# Body_Scale_v01.net
KiCad netlist of a schematic drawn in EAGLE
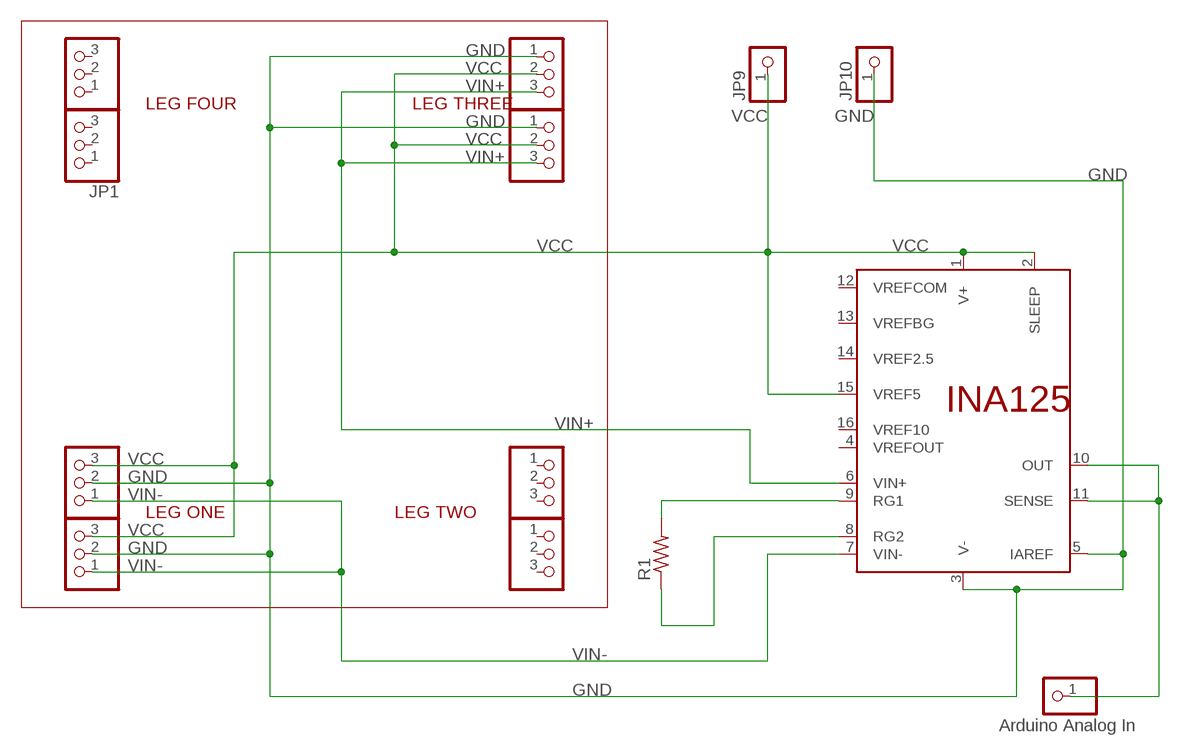
[diagram p0: schematic, sheet 1]

(export (version "E")
  (design (tool "Eeschema 10.0.6"))
  (components
    (comp (ref "IC1")
      (value "INA125")
      (footprint "eagle-import:DIL16")
      (libsource (lib "eagle-import") (part "INA125"))
    )
    (comp (ref "JP1")
      (value "PINHD-1X3")
      (footprint "eagle-import:1X03")
      (libsource (lib "eagle-import") (part "PINHD-1X3"))
    )
    (comp (ref "JP2")
      (value "PINHD-1X3")
      (footprint "eagle-import:1X03")
      (libsource (lib "eagle-import") (part "PINHD-1X3"))
    )
    (comp (ref "JP3")
      (value "PINHD-1X3")
      (footprint "eagle-import:1X03")
      (libsource (lib "eagle-import") (part "PINHD-1X3"))
    )
    (comp (ref "JP4")
      (value "PINHD-1X3")
      (footprint "eagle-import:1X03")
      (libsource (lib "eagle-import") (part "PINHD-1X3"))
    )
    (comp (ref "JP5")
      (value "PINHD-1X3")
      (footprint "eagle-import:1X03")
      (libsource (lib "eagle-import") (part "PINHD-1X3"))
    )
    (comp (ref "JP6")
      (value "PINHD-1X3")
      (footprint "eagle-import:1X03")
      (libsource (lib "eagle-import") (part "PINHD-1X3"))
    )
    (comp (ref "JP7")
      (value "PINHD-1X3")
      (footprint "eagle-import:1X03")
      (libsource (lib "eagle-import") (part "PINHD-1X3"))
    )
    (comp (ref "JP8")
      (value "PINHD-1X3")
      (footprint "eagle-import:1X03")
      (libsource (lib "eagle-import") (part "PINHD-1X3"))
    )
    (comp (ref "JP9")
      (value "PINHD-1X1")
      (footprint "eagle-import:1X01")
      (libsource (lib "eagle-import") (part "PINHD-1X1"))
    )
    (comp (ref "JP10")
      (value "PINHD-1X1")
      (footprint "eagle-import:1X01")
      (libsource (lib "eagle-import") (part "PINHD-1X1"))
    )
    (comp (ref "JP11")
      (value "PINHD-1X1")
      (footprint "eagle-import:1X01")
      (libsource (lib "eagle-import") (part "PINHD-1X1"))
    )
    (comp (ref "R1")
      (value "R-US_R0805")
      (footprint "eagle-import:R0805")
      (libsource (lib "eagle-import") (part "R-US_R0805"))
    )
  )
  (nets
    (net (code "1") (name "/GND") (class "Default")
      (node (ref "IC1") (pin "3") (pinfunction "V-_3") (pintype "bidirectional"))
      (node (ref "IC1") (pin "5") (pinfunction "IAREF_5") (pintype "bidirectional"))
      (node (ref "JP10") (pin "1") (pinfunction "1_1") (pintype "passive"))
      (node (ref "JP3") (pin "1") (pinfunction "1_1") (pintype "passive"))
      (node (ref "JP4") (pin "1") (pinfunction "1_1") (pintype "passive"))
      (node (ref "JP5") (pin "2") (pinfunction "2_2") (pintype "passive"))
      (node (ref "JP6") (pin "2") (pinfunction "2_2") (pintype "passive"))
    )
    (net (code "2") (name "/VCC") (class "Default")
      (node (ref "IC1") (pin "1") (pinfunction "V+_1") (pintype "power_in"))
      (node (ref "IC1") (pin "15") (pinfunction "VREF5_15") (pintype "output"))
      (node (ref "IC1") (pin "2") (pinfunction "SLEEP_2") (pintype "input"))
      (node (ref "JP3") (pin "2") (pinfunction "2_2") (pintype "passive"))
      (node (ref "JP4") (pin "2") (pinfunction "2_2") (pintype "passive"))
      (node (ref "JP5") (pin "3") (pinfunction "3_3") (pintype "passive"))
      (node (ref "JP6") (pin "3") (pinfunction "3_3") (pintype "passive"))
      (node (ref "JP9") (pin "1") (pinfunction "1_1") (pintype "passive"))
    )
    (net (code "3") (name "/VIN+") (class "Default")
      (node (ref "IC1") (pin "6") (pinfunction "VIN+_6") (pintype "input"))
      (node (ref "JP3") (pin "3") (pinfunction "3_3") (pintype "passive"))
      (node (ref "JP4") (pin "3") (pinfunction "3_3") (pintype "passive"))
    )
    (net (code "4") (name "/VIN-") (class "Default")
      (node (ref "IC1") (pin "7") (pinfunction "VIN-_7") (pintype "input"))
      (node (ref "JP5") (pin "1") (pinfunction "1_1") (pintype "passive"))
      (node (ref "JP6") (pin "1") (pinfunction "1_1") (pintype "passive"))
    )
    (net (code "5") (name "Net-(IC1-OUT)") (class "Default")
      (node (ref "IC1") (pin "10") (pinfunction "OUT_10") (pintype "output"))
      (node (ref "IC1") (pin "11") (pinfunction "SENSE_11") (pintype "output"))
      (node (ref "JP11") (pin "1") (pinfunction "1_1") (pintype "passive"))
    )
    (net (code "6") (name "Net-(IC1-RG1)") (class "Default")
      (node (ref "IC1") (pin "9") (pinfunction "RG1_9") (pintype "bidirectional"))
      (node (ref "R1") (pin "2") (pinfunction "2_2") (pintype "passive"))
    )
    (net (code "7") (name "Net-(IC1-RG2)") (class "Default")
      (node (ref "IC1") (pin "8") (pinfunction "RG2_8") (pintype "bidirectional"))
      (node (ref "R1") (pin "1") (pinfunction "1_1") (pintype "passive"))
    )
    (net (code "8") (name "unconnected-(IC1-VREF2.5-Pad14)") (class "Default")
      (node (ref "IC1") (pin "14") (pinfunction "VREF2.5_14") (pintype "output"))
    )
    (net (code "9") (name "unconnected-(IC1-VREF10-Pad16)") (class "Default")
      (node (ref "IC1") (pin "16") (pinfunction "VREF10_16") (pintype "output"))
    )
    (net (code "10") (name "unconnected-(IC1-VREFBG-Pad13)") (class "Default")
      (node (ref "IC1") (pin "13") (pinfunction "VREFBG_13") (pintype "output"))
    )
    (net (code "11") (name "unconnected-(IC1-VREFCOM-Pad12)") (class "Default")
      (node (ref "IC1") (pin "12") (pinfunction "VREFCOM_12") (pintype "input"))
    )
    (net (code "12") (name "unconnected-(IC1-VREFOUT-Pad4)") (class "Default")
      (node (ref "IC1") (pin "4") (pinfunction "VREFOUT_4") (pintype "output"))
    )
    (net (code "13") (name "unconnected-(JP1-Pad1)") (class "Default")
      (node (ref "JP1") (pin "1") (pinfunction "1_1") (pintype "passive"))
    )
    (net (code "14") (name "unconnected-(JP1-Pad2)") (class "Default")
      (node (ref "JP1") (pin "2") (pinfunction "2_2") (pintype "passive"))
    )
    (net (code "15") (name "unconnected-(JP1-Pad3)") (class "Default")
      (node (ref "JP1") (pin "3") (pinfunction "3_3") (pintype "passive"))
    )
    (net (code "16") (name "unconnected-(JP2-Pad1)") (class "Default")
      (node (ref "JP2") (pin "1") (pinfunction "1_1") (pintype "passive"))
    )
    (net (code "17") (name "unconnected-(JP2-Pad2)") (class "Default")
      (node (ref "JP2") (pin "2") (pinfunction "2_2") (pintype "passive"))
    )
    (net (code "18") (name "unconnected-(JP2-Pad3)") (class "Default")
      (node (ref "JP2") (pin "3") (pinfunction "3_3") (pintype "passive"))
    )
    (net (code "19") (name "unconnected-(JP7-Pad1)") (class "Default")
      (node (ref "JP7") (pin "1") (pinfunction "1_1") (pintype "passive"))
    )
    (net (code "20") (name "unconnected-(JP7-Pad2)") (class "Default")
      (node (ref "JP7") (pin "2") (pinfunction "2_2") (pintype "passive"))
    )
    (net (code "21") (name "unconnected-(JP7-Pad3)") (class "Default")
      (node (ref "JP7") (pin "3") (pinfunction "3_3") (pintype "passive"))
    )
    (net (code "22") (name "unconnected-(JP8-Pad1)") (class "Default")
      (node (ref "JP8") (pin "1") (pinfunction "1_1") (pintype "passive"))
    )
    (net (code "23") (name "unconnected-(JP8-Pad2)") (class "Default")
      (node (ref "JP8") (pin "2") (pinfunction "2_2") (pintype "passive"))
    )
    (net (code "24") (name "unconnected-(JP8-Pad3)") (class "Default")
      (node (ref "JP8") (pin "3") (pinfunction "3_3") (pintype "passive"))
    )
  )
)
